# ECG_Logic.net
KiCad netlist of a schematic drawn in EAGLE
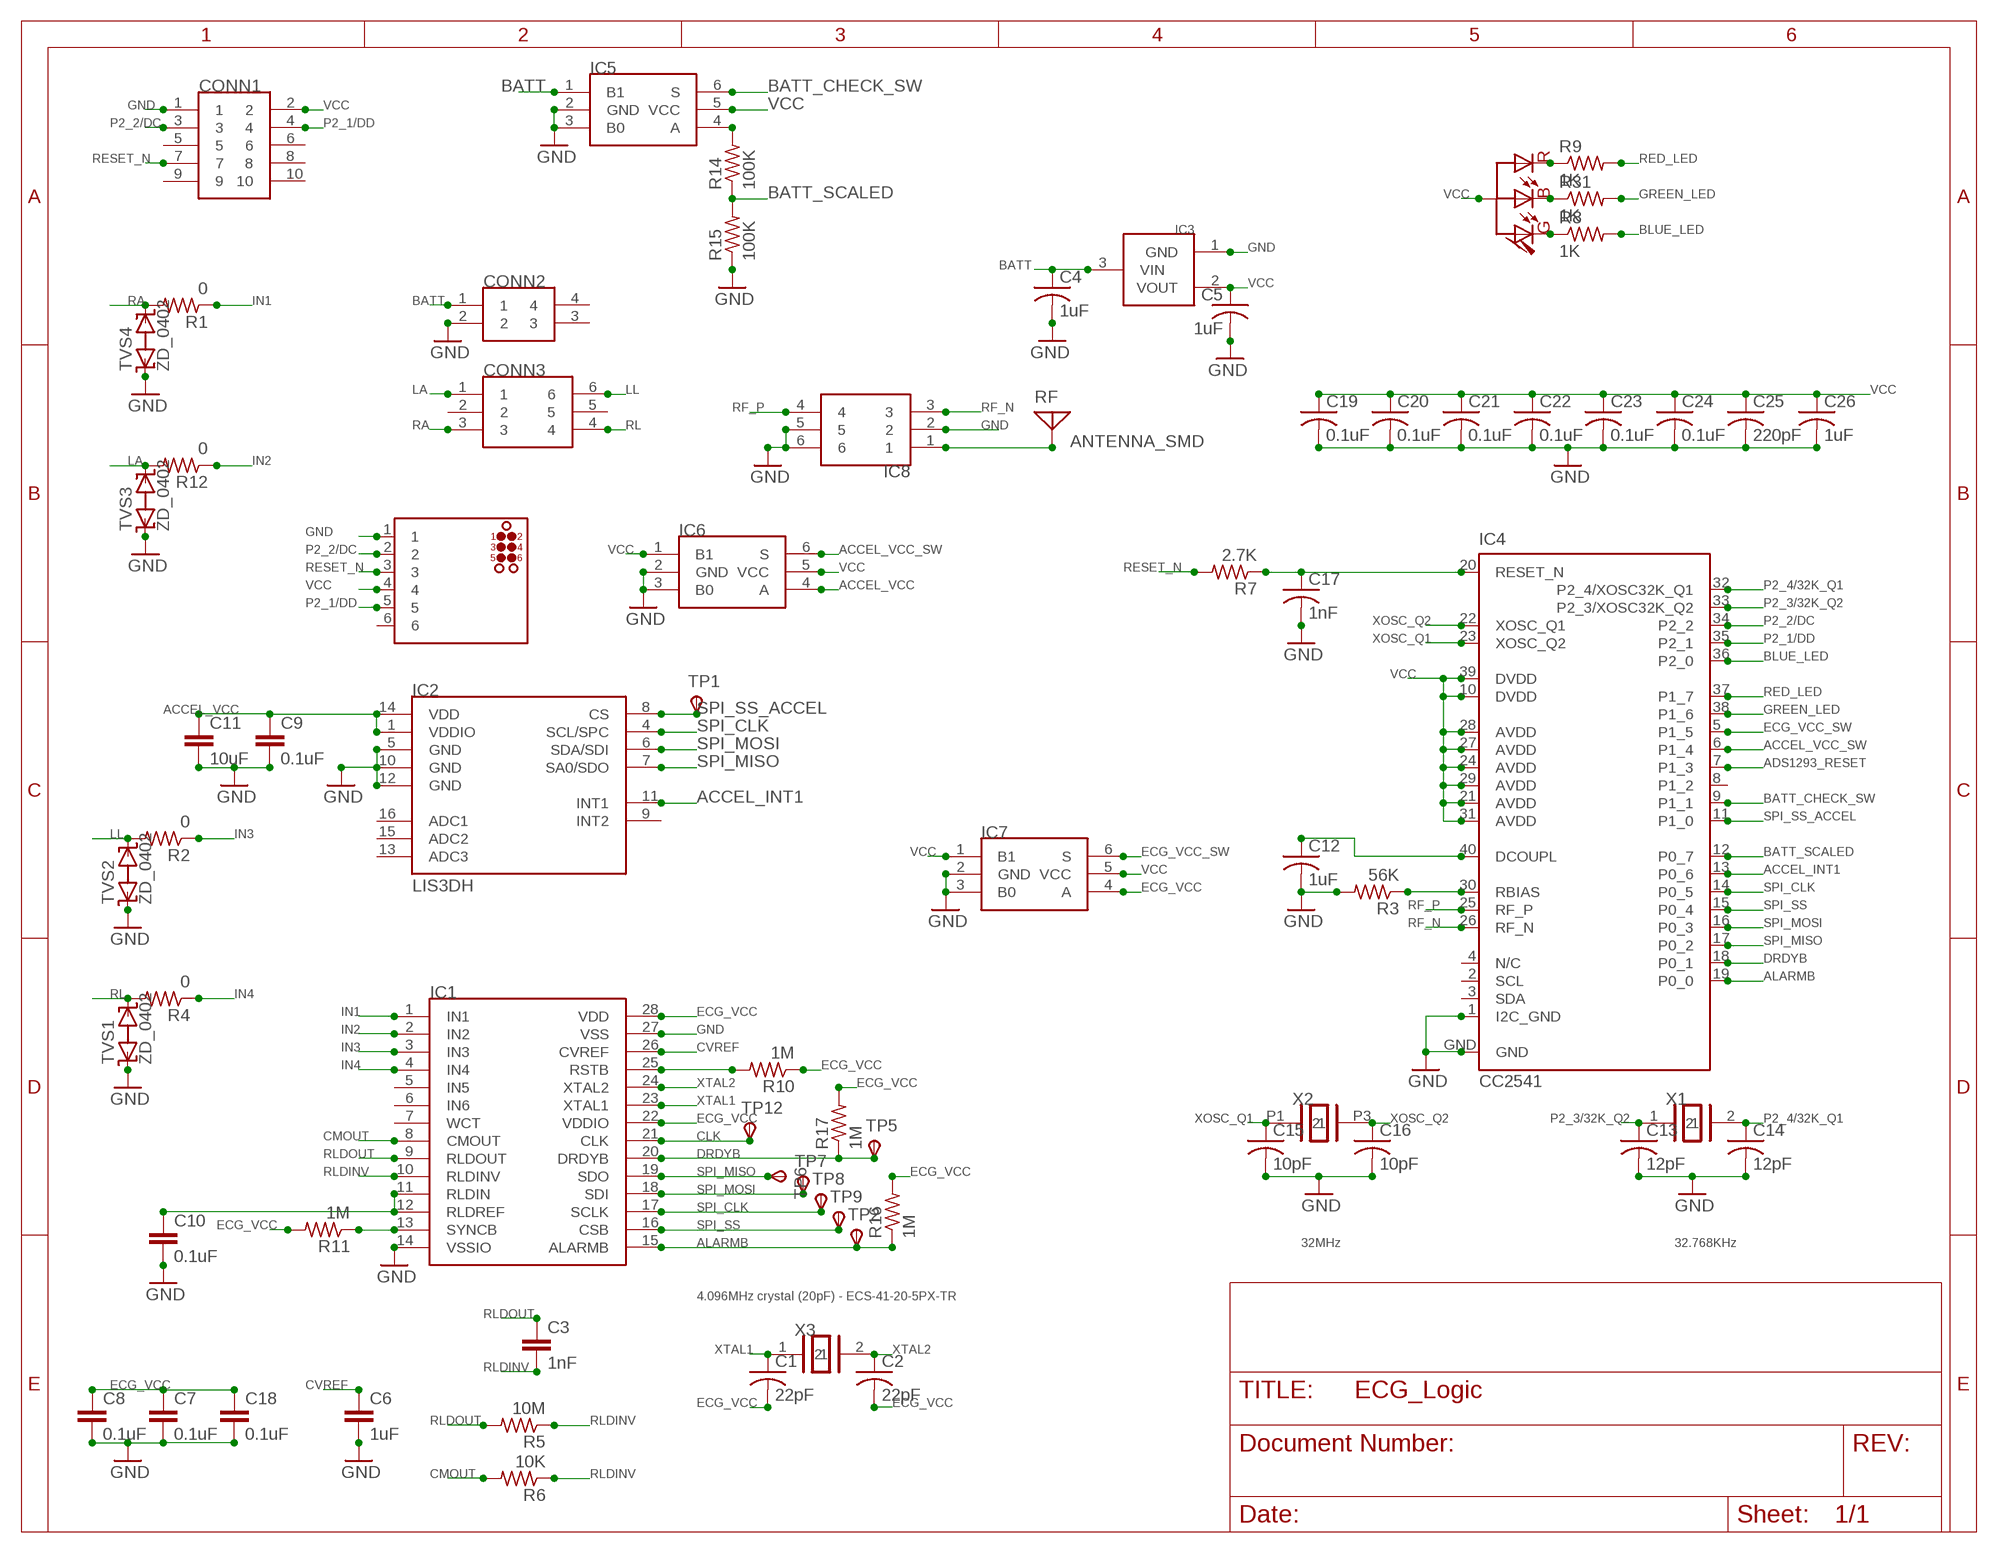
[diagram p0: schematic, sheet 1]

(export (version "E")
  (design (tool "Eeschema 10.0.6"))
  (components
    (comp (ref "C1")
      (value "22pF")
      (footprint "eagle-import:C0201")
      (libsource (lib "eagle-import") (part "C-USC0201"))
    )
    (comp (ref "C2")
      (value "22pF")
      (footprint "eagle-import:C0201")
      (libsource (lib "eagle-import") (part "C-USC0201"))
    )
    (comp (ref "C3")
      (value "1nF")
      (footprint "eagle-import:C0201")
      (libsource (lib "eagle-import") (part "C-EUC0201"))
    )
    (comp (ref "C4")
      (value "1uF")
      (footprint "eagle-import:C0201")
      (libsource (lib "eagle-import") (part "C-USC0201"))
    )
    (comp (ref "C5")
      (value "1uF")
      (footprint "eagle-import:C0201")
      (libsource (lib "eagle-import") (part "C-USC0201"))
    )
    (comp (ref "C6")
      (value "1uF")
      (footprint "eagle-import:C0201")
      (libsource (lib "eagle-import") (part "C-EUC0201"))
    )
    (comp (ref "C7")
      (value "0.1uF")
      (footprint "eagle-import:C0201")
      (libsource (lib "eagle-import") (part "C-EUC0201"))
    )
    (comp (ref "C8")
      (value "0.1uF")
      (footprint "eagle-import:C0201")
      (libsource (lib "eagle-import") (part "C-EUC0201"))
    )
    (comp (ref "C9")
      (value "0.1uF")
      (footprint "eagle-import:C0201")
      (libsource (lib "eagle-import") (part "C-EUC0201"))
    )
    (comp (ref "C10")
      (value "0.1uF")
      (footprint "eagle-import:C0201")
      (libsource (lib "eagle-import") (part "C-EUC0201"))
    )
    (comp (ref "C11")
      (value "10uF")
      (footprint "eagle-import:C0402")
      (libsource (lib "eagle-import") (part "C-EUC0402"))
    )
    (comp (ref "C12")
      (value "1uF")
      (footprint "eagle-import:C0201")
      (libsource (lib "eagle-import") (part "C-USC0201"))
    )
    (comp (ref "C13")
      (value "12pF")
      (footprint "eagle-import:C0201")
      (libsource (lib "eagle-import") (part "C-USC0201"))
    )
    (comp (ref "C14")
      (value "12pF")
      (footprint "eagle-import:C0201")
      (libsource (lib "eagle-import") (part "C-USC0201"))
    )
    (comp (ref "C15")
      (value "10pF")
      (footprint "eagle-import:C0201")
      (libsource (lib "eagle-import") (part "C-USC0201"))
    )
    (comp (ref "C16")
      (value "10pF")
      (footprint "eagle-import:C0201")
      (libsource (lib "eagle-import") (part "C-USC0201"))
    )
    (comp (ref "C17")
      (value "1nF")
      (footprint "eagle-import:C0201")
      (libsource (lib "eagle-import") (part "C-USC0201"))
    )
    (comp (ref "C18")
      (value "0.1uF")
      (footprint "eagle-import:C0201")
      (libsource (lib "eagle-import") (part "C-EUC0201"))
    )
    (comp (ref "C19")
      (value "0.1uF")
      (footprint "eagle-import:C0201")
      (libsource (lib "eagle-import") (part "C-USC0201"))
    )
    (comp (ref "C20")
      (value "0.1uF")
      (footprint "eagle-import:C0201")
      (libsource (lib "eagle-import") (part "C-USC0201"))
    )
    (comp (ref "C21")
      (value "0.1uF")
      (footprint "eagle-import:C0201")
      (libsource (lib "eagle-import") (part "C-USC0201"))
    )
    (comp (ref "C22")
      (value "0.1uF")
      (footprint "eagle-import:C0201")
      (libsource (lib "eagle-import") (part "C-USC0201"))
    )
    (comp (ref "C23")
      (value "0.1uF")
      (footprint "eagle-import:C0201")
      (libsource (lib "eagle-import") (part "C-USC0201"))
    )
    (comp (ref "C24")
      (value "0.1uF")
      (footprint "eagle-import:C0201")
      (libsource (lib "eagle-import") (part "C-USC0201"))
    )
    (comp (ref "C25")
      (value "220pF")
      (footprint "eagle-import:C0201")
      (libsource (lib "eagle-import") (part "C-USC0201"))
    )
    (comp (ref "C26")
      (value "1uF")
      (footprint "eagle-import:C0201")
      (libsource (lib "eagle-import") (part "C-USC0201"))
    )
    (comp (ref "CONN1")
      (value "10POS_1.27MM_SMD")
      (footprint "eagle-import:1.27MM_SMD")
      (libsource (lib "eagle-import") (part "10POS_1.27MM_SMD"))
    )
    (comp (ref "CONN2")
      (value "M80-4V")
      (footprint "eagle-import:M80-4-V")
      (libsource (lib "eagle-import") (part "M80-4V"))
    )
    (comp (ref "CONN3")
      (value "M80-6V")
      (footprint "eagle-import:M80-6-V")
      (libsource (lib "eagle-import") (part "M80-6V"))
    )
    (comp (ref "IC1")
      (value "ADS1293")
      (footprint "eagle-import:WQFN28")
      (libsource (lib "eagle-import") (part "ADS1293"))
    )
    (comp (ref "IC2")
      (value "LIS3DH")
      (footprint "eagle-import:LGA16-3MM")
      (libsource (lib "eagle-import") (part "LIS3DH"))
    )
    (comp (ref "IC3")
      (value "MCP1703")
      (footprint "eagle-import:SOT23")
      (libsource (lib "eagle-import") (part "MCP1703"))
    )
    (comp (ref "IC4")
      (value "CC2541")
      (footprint "eagle-import:RHA_S-PVQFN-N40")
      (libsource (lib "eagle-import") (part "CC2541"))
    )
    (comp (ref "IC5")
      (value "FSA4157")
      (footprint "eagle-import:SC70-6")
      (libsource (lib "eagle-import") (part "FSA4157"))
    )
    (comp (ref "IC6")
      (value "FSA4157")
      (footprint "eagle-import:SC70-6")
      (libsource (lib "eagle-import") (part "FSA4157"))
    )
    (comp (ref "IC7")
      (value "FSA4157")
      (footprint "eagle-import:SC70-6")
      (libsource (lib "eagle-import") (part "FSA4157"))
    )
    (comp (ref "IC8")
      (value "BALUN_2450BM_SERIES_SMD")
      (footprint "eagle-import:BALUN_SMD_2450BM_SERIES")
      (libsource (lib "eagle-import") (part "BALUN_2450BM_SERIES_SMD"))
    )
    (comp (ref "PROG")
      (value "TC2030-MCP-NL")
      (footprint "eagle-import:TC2030-MCP-NL")
      (libsource (lib "eagle-import") (part "TC2030-MCP-NL"))
    )
    (comp (ref "R1")
      (value "0")
      (footprint "eagle-import:R0201")
      (libsource (lib "eagle-import") (part "R-US_R0201"))
    )
    (comp (ref "R2")
      (value "0")
      (footprint "eagle-import:R0201")
      (libsource (lib "eagle-import") (part "R-US_R0201"))
    )
    (comp (ref "R3")
      (value "56K")
      (footprint "eagle-import:R0201")
      (libsource (lib "eagle-import") (part "R-US_R0201"))
    )
    (comp (ref "R4")
      (value "0")
      (footprint "eagle-import:R0201")
      (libsource (lib "eagle-import") (part "R-US_R0201"))
    )
    (comp (ref "R5")
      (value "10M")
      (footprint "eagle-import:R0201")
      (libsource (lib "eagle-import") (part "R-US_R0201"))
    )
    (comp (ref "R6")
      (value "10K")
      (footprint "eagle-import:R0201")
      (libsource (lib "eagle-import") (part "R-US_R0201"))
    )
    (comp (ref "R7")
      (value "2.7K")
      (footprint "eagle-import:R0201")
      (libsource (lib "eagle-import") (part "R-US_R0201"))
    )
    (comp (ref "R8")
      (value "1K")
      (footprint "eagle-import:R0201")
      (libsource (lib "eagle-import") (part "R-US_R0201"))
    )
    (comp (ref "R9")
      (value "1K")
      (footprint "eagle-import:R0201")
      (libsource (lib "eagle-import") (part "R-US_R0201"))
    )
    (comp (ref "R10")
      (value "1M")
      (footprint "eagle-import:R0201")
      (libsource (lib "eagle-import") (part "R-US_R0201"))
    )
    (comp (ref "R11")
      (value "1M")
      (footprint "eagle-import:R0201")
      (libsource (lib "eagle-import") (part "R-US_R0201"))
    )
    (comp (ref "R12")
      (value "0")
      (footprint "eagle-import:R0201")
      (libsource (lib "eagle-import") (part "R-US_R0201"))
    )
    (comp (ref "R14")
      (value "100K")
      (footprint "eagle-import:R0201")
      (libsource (lib "eagle-import") (part "R-US_R0201"))
    )
    (comp (ref "R15")
      (value "100K")
      (footprint "eagle-import:R0201")
      (libsource (lib "eagle-import") (part "R-US_R0201"))
    )
    (comp (ref "R16")
      (value "1M")
      (footprint "eagle-import:R0201")
      (libsource (lib "eagle-import") (part "R-US_R0201"))
    )
    (comp (ref "R17")
      (value "1M")
      (footprint "eagle-import:R0201")
      (libsource (lib "eagle-import") (part "R-US_R0201"))
    )
    (comp (ref "R31")
      (value "1K")
      (footprint "eagle-import:R0201")
      (libsource (lib "eagle-import") (part "R-US_R0201"))
    )
    (comp (ref "RF")
      (value "ANTENNA_SMD")
      (footprint "eagle-import:ANTENNA_SMD")
      (libsource (lib "eagle-import") (part "ANTENNA_SMD"))
    )
    (comp (ref "TP1")
      (value "TPSTP08SQ")
      (footprint "eagle-import:TP08SQ")
      (libsource (lib "eagle-import") (part "TPSTP08SQ"))
    )
    (comp (ref "TP2")
      (value "TPSTP06R")
      (footprint "eagle-import:TP06R")
      (libsource (lib "eagle-import") (part "TPSTP06R"))
    )
    (comp (ref "TP5")
      (value "TPSTP08SQ")
      (footprint "eagle-import:TP08SQ")
      (libsource (lib "eagle-import") (part "TPSTP08SQ"))
    )
    (comp (ref "TP6")
      (value "TPSTP08SQ")
      (footprint "eagle-import:TP08SQ")
      (libsource (lib "eagle-import") (part "TPSTP08SQ"))
    )
    (comp (ref "TP7")
      (value "TPSTP08SQ")
      (footprint "eagle-import:TP08SQ")
      (libsource (lib "eagle-import") (part "TPSTP08SQ"))
    )
    (comp (ref "TP8")
      (value "TPSTP08SQ")
      (footprint "eagle-import:TP08SQ")
      (libsource (lib "eagle-import") (part "TPSTP08SQ"))
    )
    (comp (ref "TP9")
      (value "TPSTP08SQ")
      (footprint "eagle-import:TP08SQ")
      (libsource (lib "eagle-import") (part "TPSTP08SQ"))
    )
    (comp (ref "TP12")
      (value "TPSTP06R")
      (footprint "eagle-import:TP06R")
      (libsource (lib "eagle-import") (part "TPSTP06R"))
    )
    (comp (ref "TRI_LED")
      (value "SML-LX0404SIUPGUSB")
      (footprint "eagle-import:SML-LX0404SIUPGUSB")
      (libsource (lib "eagle-import") (part "SML-LX0404SIUPGUSB"))
    )
    (comp (ref "TVS1")
      (value "ZD_0402")
      (footprint "eagle-import:0402")
      (libsource (lib "eagle-import") (part "ZD_0402"))
    )
    (comp (ref "TVS2")
      (value "ZD_0402")
      (footprint "eagle-import:0402")
      (libsource (lib "eagle-import") (part "ZD_0402"))
    )
    (comp (ref "TVS3")
      (value "ZD_0402")
      (footprint "eagle-import:0402")
      (libsource (lib "eagle-import") (part "ZD_0402"))
    )
    (comp (ref "TVS4")
      (value "ZD_0402")
      (footprint "eagle-import:0402")
      (libsource (lib "eagle-import") (part "ZD_0402"))
    )
    (comp (ref "X1")
      (value "XTAL-2SMD")
      (footprint "eagle-import:2-SMD")
      (libsource (lib "eagle-import") (part "XTAL-2SMD"))
    )
    (comp (ref "X2")
      (value "XTAL_403")
      (footprint "eagle-import:4-SMD")
      (libsource (lib "eagle-import") (part "XTAL_403"))
    )
    (comp (ref "X3")
      (value "XTAL-CSM7")
      (footprint "eagle-import:CSM-7")
      (libsource (lib "eagle-import") (part "XTAL-CSM7"))
    )
  )
  (nets
    (net (code "1") (name "/ACCEL_INT1") (class "Default")
      (node (ref "IC2") (pin "11") (pinfunction "INT1_11") (pintype "bidirectional"))
      (node (ref "IC4") (pin "13") (pinfunction "P0_6_13") (pintype "bidirectional"))
    )
    (net (code "2") (name "/ACCEL_VCC") (class "Default")
      (node (ref "C11") (pin "1") (pinfunction "1_1") (pintype "passive"))
      (node (ref "C9") (pin "1") (pinfunction "1_1") (pintype "passive"))
      (node (ref "IC2") (pin "1") (pinfunction "VDDIO_1") (pintype "bidirectional"))
      (node (ref "IC2") (pin "14") (pinfunction "VDD_14") (pintype "bidirectional"))
      (node (ref "IC6") (pin "4") (pinfunction "A_4") (pintype "bidirectional"))
    )
    (net (code "3") (name "/ACCEL_VCC_SW") (class "Default")
      (node (ref "IC4") (pin "6") (pinfunction "P1_4_6") (pintype "bidirectional"))
      (node (ref "IC6") (pin "6") (pinfunction "S_6") (pintype "bidirectional"))
    )
    (net (code "4") (name "/ADS1293_RESET") (class "Default")
      (node (ref "IC4") (pin "7") (pinfunction "P1_3_7") (pintype "bidirectional"))
    )
    (net (code "5") (name "/ALARMB") (class "Default")
      (node (ref "IC1") (pin "15") (pinfunction "ALARMB_15") (pintype "bidirectional"))
      (node (ref "IC4") (pin "19") (pinfunction "P0_0_19") (pintype "bidirectional"))
      (node (ref "R16") (pin "1") (pinfunction "1_1") (pintype "passive"))
      (node (ref "TP2") (pin "TP") (pinfunction "PP_TP") (pintype "input"))
    )
    (net (code "6") (name "/BATT") (class "Default")
      (node (ref "C4") (pin "1") (pinfunction "1_1") (pintype "passive"))
      (node (ref "CONN2") (pin "1") (pinfunction "1_1") (pintype "bidirectional"))
      (node (ref "IC3") (pin "3") (pinfunction "VIN_3") (pintype "bidirectional"))
      (node (ref "IC5") (pin "1") (pinfunction "B1_1") (pintype "bidirectional"))
    )
    (net (code "7") (name "/BATT_CHECK_SW") (class "Default")
      (node (ref "IC4") (pin "9") (pinfunction "P1_1_9") (pintype "bidirectional"))
      (node (ref "IC5") (pin "6") (pinfunction "S_6") (pintype "bidirectional"))
    )
    (net (code "8") (name "/BATT_SCALED") (class "Default")
      (node (ref "IC4") (pin "12") (pinfunction "P0_7_12") (pintype "bidirectional"))
      (node (ref "R14") (pin "1") (pinfunction "1_1") (pintype "passive"))
      (node (ref "R15") (pin "2") (pinfunction "2_2") (pintype "passive"))
    )
    (net (code "9") (name "/BLUE_LED") (class "Default")
      (node (ref "IC4") (pin "36") (pinfunction "P2_0_36") (pintype "bidirectional"))
      (node (ref "R8") (pin "2") (pinfunction "2_2") (pintype "passive"))
    )
    (net (code "10") (name "/CLK") (class "Default")
      (node (ref "IC1") (pin "21") (pinfunction "CLK_21") (pintype "bidirectional"))
      (node (ref "TP12") (pin "TP") (pinfunction "PP_TP") (pintype "input"))
    )
    (net (code "11") (name "/CMOUT") (class "Default")
      (node (ref "IC1") (pin "8") (pinfunction "CMOUT_8") (pintype "bidirectional"))
      (node (ref "R6") (pin "2") (pinfunction "2_2") (pintype "passive"))
    )
    (net (code "12") (name "/CVREF") (class "Default")
      (node (ref "C6") (pin "1") (pinfunction "1_1") (pintype "passive"))
      (node (ref "IC1") (pin "26") (pinfunction "CVREF_26") (pintype "bidirectional"))
    )
    (net (code "13") (name "/DRDYB") (class "Default")
      (node (ref "IC1") (pin "20") (pinfunction "DRDYB_20") (pintype "bidirectional"))
      (node (ref "IC4") (pin "18") (pinfunction "P0_1_18") (pintype "bidirectional"))
      (node (ref "R17") (pin "1") (pinfunction "1_1") (pintype "passive"))
      (node (ref "TP5") (pin "TP") (pinfunction "PP_TP") (pintype "input"))
    )
    (net (code "14") (name "/ECG_VCC") (class "Default")
      (node (ref "C1") (pin "2") (pinfunction "2_2") (pintype "passive"))
      (node (ref "C18") (pin "1") (pinfunction "1_1") (pintype "passive"))
      (node (ref "C2") (pin "2") (pinfunction "2_2") (pintype "passive"))
      (node (ref "C7") (pin "1") (pinfunction "1_1") (pintype "passive"))
      (node (ref "C8") (pin "1") (pinfunction "1_1") (pintype "passive"))
      (node (ref "IC1") (pin "22") (pinfunction "VDDIO_22") (pintype "bidirectional"))
      (node (ref "IC1") (pin "28") (pinfunction "VDD_28") (pintype "bidirectional"))
      (node (ref "IC7") (pin "4") (pinfunction "A_4") (pintype "bidirectional"))
      (node (ref "R10") (pin "1") (pinfunction "1_1") (pintype "passive"))
      (node (ref "R11") (pin "2") (pinfunction "2_2") (pintype "passive"))
      (node (ref "R16") (pin "2") (pinfunction "2_2") (pintype "passive"))
      (node (ref "R17") (pin "2") (pinfunction "2_2") (pintype "passive"))
    )
    (net (code "15") (name "/ECG_VCC_SW") (class "Default")
      (node (ref "IC4") (pin "5") (pinfunction "P1_5_5") (pintype "bidirectional"))
      (node (ref "IC7") (pin "6") (pinfunction "S_6") (pintype "bidirectional"))
    )
    (net (code "16") (name "/GREEN_LED") (class "Default")
      (node (ref "IC4") (pin "38") (pinfunction "P1_6_38") (pintype "bidirectional"))
      (node (ref "R31") (pin "2") (pinfunction "2_2") (pintype "passive"))
    )
    (net (code "17") (name "/IN1") (class "Default")
      (node (ref "IC1") (pin "1") (pinfunction "IN1_1") (pintype "bidirectional"))
      (node (ref "R1") (pin "1") (pinfunction "1_1") (pintype "passive"))
    )
    (net (code "18") (name "/IN2") (class "Default")
      (node (ref "IC1") (pin "2") (pinfunction "IN2_2") (pintype "bidirectional"))
      (node (ref "R12") (pin "1") (pinfunction "1_1") (pintype "passive"))
    )
    (net (code "19") (name "/IN3") (class "Default")
      (node (ref "IC1") (pin "3") (pinfunction "IN3_3") (pintype "bidirectional"))
      (node (ref "R2") (pin "1") (pinfunction "1_1") (pintype "passive"))
    )
    (net (code "20") (name "/IN4") (class "Default")
      (node (ref "IC1") (pin "4") (pinfunction "IN4_4") (pintype "bidirectional"))
      (node (ref "R4") (pin "1") (pinfunction "1_1") (pintype "passive"))
    )
    (net (code "21") (name "/LA") (class "Default")
      (node (ref "CONN3") (pin "1") (pinfunction "1_1") (pintype "bidirectional"))
      (node (ref "R12") (pin "2") (pinfunction "2_2") (pintype "passive"))
      (node (ref "TVS3") (pin "2") (pinfunction "C_2") (pintype "passive"))
    )
    (net (code "22") (name "/LL") (class "Default")
      (node (ref "CONN3") (pin "6") (pinfunction "6_6") (pintype "bidirectional"))
      (node (ref "R2") (pin "2") (pinfunction "2_2") (pintype "passive"))
      (node (ref "TVS2") (pin "2") (pinfunction "C_2") (pintype "passive"))
    )
    (net (code "23") (name "/N{slash}C") (class "Default")
      (node (ref "IC4") (pin "4") (pinfunction "N/C_4") (pintype "power_in"))
    )
    (net (code "24") (name "/P2_1{slash}DD") (class "Default")
      (node (ref "CONN1") (pin "4") (pinfunction "4_4") (pintype "bidirectional"))
      (node (ref "IC4") (pin "35") (pinfunction "P2_1_35") (pintype "bidirectional"))
      (node (ref "PROG") (pin "5") (pinfunction "5_5") (pintype "output"))
    )
    (net (code "25") (name "/P2_2{slash}DC") (class "Default")
      (node (ref "CONN1") (pin "3") (pinfunction "3_3") (pintype "bidirectional"))
      (node (ref "IC4") (pin "34") (pinfunction "P2_2_34") (pintype "bidirectional"))
      (node (ref "PROG") (pin "2") (pinfunction "2_2") (pintype "power_in"))
    )
    (net (code "26") (name "/P2_3{slash}32K_Q2") (class "Default")
      (node (ref "C13") (pin "1") (pinfunction "1_1") (pintype "passive"))
      (node (ref "IC4") (pin "33") (pinfunction "P2_3/XOSC32K_Q2_33") (pintype "bidirectional"))
      (node (ref "X1") (pin "1") (pinfunction "1_1") (pintype "bidirectional"))
    )
    (net (code "27") (name "/P2_4{slash}32K_Q1") (class "Default")
      (node (ref "C14") (pin "1") (pinfunction "1_1") (pintype "passive"))
      (node (ref "IC4") (pin "32") (pinfunction "P2_4/XOSC32K_Q1_32") (pintype "bidirectional"))
      (node (ref "X1") (pin "2") (pinfunction "2_2") (pintype "bidirectional"))
    )
    (net (code "28") (name "/RA") (class "Default")
      (node (ref "CONN3") (pin "3") (pinfunction "3_3") (pintype "bidirectional"))
      (node (ref "R1") (pin "2") (pinfunction "2_2") (pintype "passive"))
      (node (ref "TVS4") (pin "2") (pinfunction "C_2") (pintype "passive"))
    )
    (net (code "29") (name "/RED_LED") (class "Default")
      (node (ref "IC4") (pin "37") (pinfunction "P1_7_37") (pintype "bidirectional"))
      (node (ref "R9") (pin "2") (pinfunction "2_2") (pintype "passive"))
    )
    (net (code "30") (name "/RESET_N") (class "Default")
      (node (ref "CONN1") (pin "7") (pinfunction "7_7") (pintype "bidirectional"))
      (node (ref "PROG") (pin "3") (pinfunction "3_3") (pintype "power_in"))
      (node (ref "R7") (pin "2") (pinfunction "2_2") (pintype "passive"))
    )
    (net (code "31") (name "/RF_N") (class "Default")
      (node (ref "IC4") (pin "26") (pinfunction "RF_N_26") (pintype "bidirectional"))
      (node (ref "IC8") (pin "3") (pinfunction "3_3") (pintype "bidirectional"))
    )
    (net (code "32") (name "/RF_P") (class "Default")
      (node (ref "IC4") (pin "25") (pinfunction "RF_P_25") (pintype "bidirectional"))
      (node (ref "IC8") (pin "4") (pinfunction "4_4") (pintype "bidirectional"))
    )
    (net (code "33") (name "/RL") (class "Default")
      (node (ref "CONN3") (pin "4") (pinfunction "4_4") (pintype "bidirectional"))
      (node (ref "R4") (pin "2") (pinfunction "2_2") (pintype "passive"))
      (node (ref "TVS1") (pin "2") (pinfunction "C_2") (pintype "passive"))
    )
    (net (code "34") (name "/RLDINV") (class "Default")
      (node (ref "C3") (pin "2") (pinfunction "2_2") (pintype "passive"))
      (node (ref "IC1") (pin "10") (pinfunction "RLDINV_10") (pintype "bidirectional"))
      (node (ref "R5") (pin "1") (pinfunction "1_1") (pintype "passive"))
      (node (ref "R6") (pin "1") (pinfunction "1_1") (pintype "passive"))
    )
    (net (code "35") (name "/RLDOUT") (class "Default")
      (node (ref "C3") (pin "1") (pinfunction "1_1") (pintype "passive"))
      (node (ref "IC1") (pin "9") (pinfunction "RLDOUT_9") (pintype "bidirectional"))
      (node (ref "R5") (pin "2") (pinfunction "2_2") (pintype "passive"))
    )
    (net (code "36") (name "/SPI_CLK") (class "Default")
      (node (ref "IC1") (pin "17") (pinfunction "SCLK_17") (pintype "bidirectional"))
      (node (ref "IC2") (pin "4") (pinfunction "SCL/SPC_4") (pintype "bidirectional"))
      (node (ref "IC4") (pin "14") (pinfunction "P0_5_14") (pintype "bidirectional"))
      (node (ref "TP8") (pin "TP") (pinfunction "PP_TP") (pintype "input"))
    )
    (net (code "37") (name "/SPI_MISO") (class "Default")
      (node (ref "IC1") (pin "19") (pinfunction "SDO_19") (pintype "bidirectional"))
      (node (ref "IC2") (pin "7") (pinfunction "SA0/SDO_7") (pintype "bidirectional"))
      (node (ref "IC4") (pin "17") (pinfunction "P0_2_17") (pintype "bidirectional"))
      (node (ref "TP6") (pin "TP") (pinfunction "PP_TP") (pintype "input"))
    )
    (net (code "38") (name "/SPI_MOSI") (class "Default")
      (node (ref "IC1") (pin "18") (pinfunction "SDI_18") (pintype "bidirectional"))
      (node (ref "IC2") (pin "6") (pinfunction "SDA/SDI_6") (pintype "bidirectional"))
      (node (ref "IC4") (pin "16") (pinfunction "P0_3_16") (pintype "bidirectional"))
      (node (ref "TP7") (pin "TP") (pinfunction "PP_TP") (pintype "input"))
    )
    (net (code "39") (name "/SPI_SS") (class "Default")
      (node (ref "IC1") (pin "16") (pinfunction "CSB_16") (pintype "bidirectional"))
      (node (ref "IC4") (pin "15") (pinfunction "P0_4_15") (pintype "bidirectional"))
      (node (ref "TP9") (pin "TP") (pinfunction "PP_TP") (pintype "input"))
    )
    (net (code "40") (name "/SPI_SS_ACCEL") (class "Default")
      (node (ref "IC2") (pin "8") (pinfunction "CS_8") (pintype "bidirectional"))
      (node (ref "IC4") (pin "11") (pinfunction "P1_0_11") (pintype "bidirectional"))
      (node (ref "TP1") (pin "TP") (pinfunction "PP_TP") (pintype "input"))
    )
    (net (code "41") (name "/VCC") (class "Default")
      (node (ref "C19") (pin "1") (pinfunction "1_1") (pintype "passive"))
      (node (ref "C20") (pin "1") (pinfunction "1_1") (pintype "passive"))
      (node (ref "C21") (pin "1") (pinfunction "1_1") (pintype "passive"))
      (node (ref "C22") (pin "1") (pinfunction "1_1") (pintype "passive"))
      (node (ref "C23") (pin "1") (pinfunction "1_1") (pintype "passive"))
      (node (ref "C24") (pin "1") (pinfunction "1_1") (pintype "passive"))
      (node (ref "C25") (pin "1") (pinfunction "1_1") (pintype "passive"))
      (node (ref "C26") (pin "1") (pinfunction "1_1") (pintype "passive"))
      (node (ref "C5") (pin "1") (pinfunction "1_1") (pintype "passive"))
      (node (ref "CONN1") (pin "2") (pinfunction "2_2") (pintype "bidirectional"))
      (node (ref "IC3") (pin "2") (pinfunction "VOUT_2") (pintype "bidirectional"))
      (node (ref "IC4") (pin "10") (pinfunction "DVDD_10") (pintype "power_in"))
      (node (ref "IC4") (pin "21") (pinfunction "AVDD_21") (pintype "power_in"))
      (node (ref "IC4") (pin "24") (pinfunction "AVDD_24") (pintype "power_in"))
      (node (ref "IC4") (pin "27") (pinfunction "AVDD_27") (pintype "power_in"))
      (node (ref "IC4") (pin "28") (pinfunction "AVDD_28") (pintype "power_in"))
      (node (ref "IC4") (pin "29") (pinfunction "AVDD_29") (pintype "power_in"))
      (node (ref "IC4") (pin "31") (pinfunction "AVDD_31") (pintype "power_in"))
      (node (ref "IC4") (pin "39") (pinfunction "DVDD_39") (pintype "power_in"))
      (node (ref "IC5") (pin "5") (pinfunction "VCC_5") (pintype "bidirectional"))
      (node (ref "IC6") (pin "1") (pinfunction "B1_1") (pintype "bidirectional"))
      (node (ref "IC6") (pin "5") (pinfunction "VCC_5") (pintype "bidirectional"))
      (node (ref "IC7") (pin "1") (pinfunction "B1_1") (pintype "bidirectional"))
      (node (ref "IC7") (pin "5") (pinfunction "VCC_5") (pintype "bidirectional"))
      (node (ref "PROG") (pin "4") (pinfunction "4_4") (pintype "bidirectional"))
      (node (ref "TRI_LED") (pin "1") (pinfunction "A_1") (pintype "passive"))
    )
    (net (code "42") (name "/XOSC_Q1") (class "Default")
      (node (ref "C15") (pin "1") (pinfunction "1_1") (pintype "passive"))
      (node (ref "IC4") (pin "23") (pinfunction "XOSC_Q2_23") (pintype "bidirectional"))
      (node (ref "X2") (pin "P1") (pinfunction "1_P1") (pintype "bidirectional"))
    )
    (net (code "43") (name "/XOSC_Q2") (class "Default")
      (node (ref "C16") (pin "1") (pinfunction "1_1") (pintype "passive"))
      (node (ref "IC4") (pin "22") (pinfunction "XOSC_Q1_22") (pintype "bidirectional"))
      (node (ref "X2") (pin "P3") (pinfunction "2_P3") (pintype "bidirectional"))
    )
    (net (code "44") (name "/XTAL1") (class "Default")
      (node (ref "C1") (pin "1") (pinfunction "1_1") (pintype "passive"))
      (node (ref "IC1") (pin "23") (pinfunction "XTAL1_23") (pintype "bidirectional"))
      (node (ref "X3") (pin "1") (pinfunction "1_1") (pintype "bidirectional"))
    )
    (net (code "45") (name "/XTAL2") (class "Default")
      (node (ref "C2") (pin "1") (pinfunction "1_1") (pintype "passive"))
      (node (ref "IC1") (pin "24") (pinfunction "XTAL2_24") (pintype "bidirectional"))
      (node (ref "X3") (pin "2") (pinfunction "2_2") (pintype "bidirectional"))
    )
    (net (code "46") (name "GND") (class "Default")
      (node (ref "C10") (pin "2") (pinfunction "2_2") (pintype "passive"))
      (node (ref "C11") (pin "2") (pinfunction "2_2") (pintype "passive"))
      (node (ref "C12") (pin "2") (pinfunction "2_2") (pintype "passive"))
      (node (ref "C13") (pin "2") (pinfunction "2_2") (pintype "passive"))
      (node (ref "C14") (pin "2") (pinfunction "2_2") (pintype "passive"))
      (node (ref "C15") (pin "2") (pinfunction "2_2") (pintype "passive"))
      (node (ref "C16") (pin "2") (pinfunction "2_2") (pintype "passive"))
      (node (ref "C17") (pin "2") (pinfunction "2_2") (pintype "passive"))
      (node (ref "C18") (pin "2") (pinfunction "2_2") (pintype "passive"))
      (node (ref "C19") (pin "2") (pinfunction "2_2") (pintype "passive"))
      (node (ref "C20") (pin "2") (pinfunction "2_2") (pintype "passive"))
      (node (ref "C21") (pin "2") (pinfunction "2_2") (pintype "passive"))
      (node (ref "C22") (pin "2") (pinfunction "2_2") (pintype "passive"))
      (node (ref "C23") (pin "2") (pinfunction "2_2") (pintype "passive"))
      (node (ref "C24") (pin "2") (pinfunction "2_2") (pintype "passive"))
      (node (ref "C25") (pin "2") (pinfunction "2_2") (pintype "passive"))
      (node (ref "C26") (pin "2") (pinfunction "2_2") (pintype "passive"))
      (node (ref "C4") (pin "2") (pinfunction "2_2") (pintype "passive"))
      (node (ref "C5") (pin "2") (pinfunction "2_2") (pintype "passive"))
      (node (ref "C6") (pin "2") (pinfunction "2_2") (pintype "passive"))
      (node (ref "C7") (pin "2") (pinfunction "2_2") (pintype "passive"))
      (node (ref "C8") (pin "2") (pinfunction "2_2") (pintype "passive"))
      (node (ref "C9") (pin "2") (pinfunction "2_2") (pintype "passive"))
      (node (ref "CONN1") (pin "1") (pinfunction "1_1") (pintype "bidirectional"))
      (node (ref "CONN2") (pin "2") (pinfunction "2_2") (pintype "bidirectional"))
      (node (ref "IC1") (pin "14") (pinfunction "VSSIO_14") (pintype "bidirectional"))
      (node (ref "IC1") (pin "27") (pinfunction "VSS_27") (pintype "bidirectional"))
      (node (ref "IC2") (pin "10") (pinfunction "GND_10") (pintype "bidirectional"))
      (node (ref "IC2") (pin "12") (pinfunction "GND_12") (pintype "bidirectional"))
      (node (ref "IC2") (pin "5") (pinfunction "GND_5") (pintype "bidirectional"))
      (node (ref "IC3") (pin "1") (pinfunction "GND_1") (pintype "bidirectional"))
      (node (ref "IC4") (pin "1") (pinfunction "I2C_GND_1") (pintype "power_in"))
      (node (ref "IC4") (pin "GND") (pinfunction "GND_GND") (pintype "passive"))
      (node (ref "IC5") (pin "2") (pinfunction "GND_2") (pintype "bidirectional"))
      (node (ref "IC5") (pin "3") (pinfunction "B0_3") (pintype "bidirectional"))
      (node (ref "IC6") (pin "2") (pinfunction "GND_2") (pintype "bidirectional"))
      (node (ref "IC6") (pin "3") (pinfunction "B0_3") (pintype "bidirectional"))
      (node (ref "IC7") (pin "2") (pinfunction "GND_2") (pintype "bidirectional"))
      (node (ref "IC7") (pin "3") (pinfunction "B0_3") (pintype "bidirectional"))
      (node (ref "IC8") (pin "2") (pinfunction "2_2") (pintype "bidirectional"))
      (node (ref "IC8") (pin "5") (pinfunction "5_5") (pintype "bidirectional"))
      (node (ref "IC8") (pin "6") (pinfunction "6_6") (pintype "bidirectional"))
      (node (ref "PROG") (pin "1") (pinfunction "1_1") (pintype "passive"))
      (node (ref "R15") (pin "1") (pinfunction "1_1") (pintype "passive"))
      (node (ref "R3") (pin "2") (pinfunction "2_2") (pintype "passive"))
      (node (ref "TVS1") (pin "1") (pinfunction "A_1") (pintype "passive"))
      (node (ref "TVS2") (pin "1") (pinfunction "A_1") (pintype "passive"))
      (node (ref "TVS3") (pin "1") (pinfunction "A_1") (pintype "passive"))
      (node (ref "TVS4") (pin "1") (pinfunction "A_1") (pintype "passive"))
    )
    (net (code "47") (name "Net-(IC1-RLDIN)") (class "Default")
      (node (ref "C10") (pin "1") (pinfunction "1_1") (pintype "passive"))
      (node (ref "IC1") (pin "11") (pinfunction "RLDIN_11") (pintype "bidirectional"))
      (node (ref "IC1") (pin "12") (pinfunction "RLDREF_12") (pintype "bidirectional"))
    )
    (net (code "48") (name "Net-(IC1-RSTB)") (class "Default")
      (node (ref "IC1") (pin "25") (pinfunction "RSTB_25") (pintype "bidirectional"))
      (node (ref "R10") (pin "2") (pinfunction "2_2") (pintype "passive"))
    )
    (net (code "49") (name "Net-(IC1-SYNCB)") (class "Default")
      (node (ref "IC1") (pin "13") (pinfunction "SYNCB_13") (pintype "bidirectional"))
      (node (ref "R11") (pin "1") (pinfunction "1_1") (pintype "passive"))
    )
    (net (code "50") (name "Net-(IC4-DCOUPL)") (class "Default")
      (node (ref "C12") (pin "1") (pinfunction "1_1") (pintype "passive"))
      (node (ref "IC4") (pin "40") (pinfunction "DCOUPL_40") (pintype "power_in"))
    )
    (net (code "51") (name "Net-(IC4-RBIAS)") (class "Default")
      (node (ref "IC4") (pin "30") (pinfunction "RBIAS_30") (pintype "bidirectional"))
      (node (ref "R3") (pin "1") (pinfunction "1_1") (pintype "passive"))
    )
    (net (code "52") (name "Net-(IC4-RESET_N)") (class "Default")
      (node (ref "C17") (pin "1") (pinfunction "1_1") (pintype "passive"))
      (node (ref "IC4") (pin "20") (pinfunction "RESET_N_20") (pintype "input"))
      (node (ref "R7") (pin "1") (pinfunction "1_1") (pintype "passive"))
    )
    (net (code "53") (name "Net-(IC5-A)") (class "Default")
      (node (ref "IC5") (pin "4") (pinfunction "A_4") (pintype "bidirectional"))
      (node (ref "R14") (pin "2") (pinfunction "2_2") (pintype "passive"))
    )
    (net (code "54") (name "Net-(IC8-Pad1)") (class "Default")
      (node (ref "IC8") (pin "1") (pinfunction "1_1") (pintype "bidirectional"))
      (node (ref "RF") (pin "1") (pinfunction "1_1") (pintype "output"))
    )
    (net (code "55") (name "Net-(TRI_LED-B)") (class "Default")
      (node (ref "R9") (pin "1") (pinfunction "1_1") (pintype "passive"))
      (node (ref "TRI_LED") (pin "3") (pinfunction "B_3") (pintype "passive"))
    )
    (net (code "56") (name "Net-(TRI_LED-G)") (class "Default")
      (node (ref "R31") (pin "1") (pinfunction "1_1") (pintype "passive"))
      (node (ref "TRI_LED") (pin "4") (pinfunction "G_4") (pintype "passive"))
    )
    (net (code "57") (name "Net-(TRI_LED-R)") (class "Default")
      (node (ref "R8") (pin "1") (pinfunction "1_1") (pintype "passive"))
      (node (ref "TRI_LED") (pin "2") (pinfunction "R_2") (pintype "passive"))
    )
    (net (code "58") (name "unconnected-(CONN1-Pad5)") (class "Default")
      (node (ref "CONN1") (pin "5") (pinfunction "5_5") (pintype "bidirectional"))
    )
    (net (code "59") (name "unconnected-(CONN1-Pad6)") (class "Default")
      (node (ref "CONN1") (pin "6") (pinfunction "6_6") (pintype "bidirectional"))
    )
    (net (code "60") (name "unconnected-(CONN1-Pad8)") (class "Default")
      (node (ref "CONN1") (pin "8") (pinfunction "8_8") (pintype "bidirectional"))
    )
    (net (code "61") (name "unconnected-(CONN1-Pad9)") (class "Default")
      (node (ref "CONN1") (pin "9") (pinfunction "9_9") (pintype "bidirectional"))
    )
    (net (code "62") (name "unconnected-(CONN1-Pad10)") (class "Default")
      (node (ref "CONN1") (pin "10") (pinfunction "10_10") (pintype "bidirectional"))
    )
    (net (code "63") (name "unconnected-(CONN2-Pad3)") (class "Default")
      (node (ref "CONN2") (pin "3") (pinfunction "3_3") (pintype "bidirectional"))
    )
    (net (code "64") (name "unconnected-(CONN2-Pad4)") (class "Default")
      (node (ref "CONN2") (pin "4") (pinfunction "4_4") (pintype "bidirectional"))
    )
    (net (code "65") (name "unconnected-(CONN3-Pad2)") (class "Default")
      (node (ref "CONN3") (pin "2") (pinfunction "2_2") (pintype "bidirectional"))
    )
    (net (code "66") (name "unconnected-(CONN3-Pad5)") (class "Default")
      (node (ref "CONN3") (pin "5") (pinfunction "5_5") (pintype "bidirectional"))
    )
    (net (code "67") (name "unconnected-(IC1-IN5-Pad5)") (class "Default")
      (node (ref "IC1") (pin "5") (pinfunction "IN5_5") (pintype "bidirectional"))
    )
    (net (code "68") (name "unconnected-(IC1-IN6-Pad6)") (class "Default")
      (node (ref "IC1") (pin "6") (pinfunction "IN6_6") (pintype "bidirectional"))
    )
    (net (code "69") (name "unconnected-(IC1-WCT-Pad7)") (class "Default")
      (node (ref "IC1") (pin "7") (pinfunction "WCT_7") (pintype "bidirectional"))
    )
    (net (code "70") (name "unconnected-(IC2-ADC1-Pad16)") (class "Default")
      (node (ref "IC2") (pin "16") (pinfunction "ADC1_16") (pintype "bidirectional"))
    )
    (net (code "71") (name "unconnected-(IC2-ADC2-Pad15)") (class "Default")
      (node (ref "IC2") (pin "15") (pinfunction "ADC2_15") (pintype "bidirectional"))
    )
    (net (code "72") (name "unconnected-(IC2-ADC3-Pad13)") (class "Default")
      (node (ref "IC2") (pin "13") (pinfunction "ADC3_13") (pintype "bidirectional"))
    )
    (net (code "73") (name "unconnected-(IC2-INT2-Pad9)") (class "Default")
      (node (ref "IC2") (pin "9") (pinfunction "INT2_9") (pintype "bidirectional"))
    )
    (net (code "74") (name "unconnected-(IC4-P1_2-Pad8)") (class "Default")
      (node (ref "IC4") (pin "8") (pinfunction "P1_2_8") (pintype "bidirectional"))
    )
    (net (code "75") (name "unconnected-(IC4-SCL-Pad2)") (class "Default")
      (node (ref "IC4") (pin "2") (pinfunction "SCL_2") (pintype "bidirectional"))
    )
    (net (code "76") (name "unconnected-(IC4-SDA-Pad3)") (class "Default")
      (node (ref "IC4") (pin "3") (pinfunction "SDA_3") (pintype "bidirectional"))
    )
    (net (code "77") (name "unconnected-(PROG-Pad6)") (class "Default")
      (node (ref "PROG") (pin "6") (pinfunction "6_6") (pintype "bidirectional"))
    )
  )
)
